# LED_ALERT.net
KiCad netlist of a schematic drawn in Altium Designer
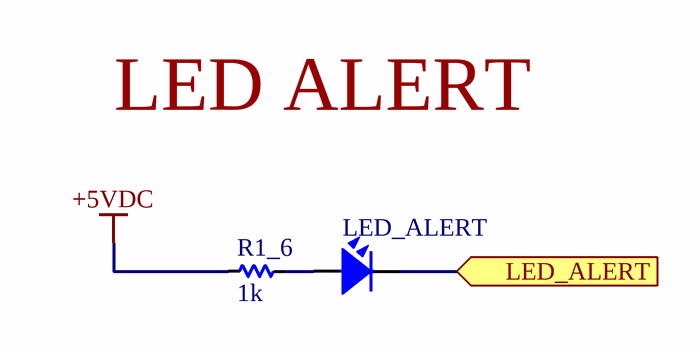
[diagram p0: LED_ALERT.SchDoc]

(export (version "E")
  (design (tool "Eeschema 10.0.6"))
  (components
    (comp (ref "LED_ALERT")
      (value "LED")
      (footprint "LED-3MM-GREEN")
      (description "LED Single colour Green and Red")
      (libsource (lib "Altium Library") (part "LED"))
    )
    (comp (ref "R1_6")
      (value "1k")
      (footprint "RES-SMD-0805")
      (description "Resistor")
      (fields
        (field (name "MANUFACTURER") "Generic Components")
        (field (name "PUBLISHER") "Altium Hobart Technology Centre")
      )
      (libsource (lib "Altium Library") (part "Res-SMD"))
    )
  )
  (nets
    (net (code "1") (name "+5VDC") (class "Default")
      (node (ref "R1_6") (pin "2") (pinfunction "2_2") (pintype "passive"))
    )
    (net (code "2") (name "/LED_ALERT") (class "Default")
      (node (ref "LED_ALERT") (pin "2") (pinfunction "2_2") (pintype "passive"))
    )
    (net (code "3") (name "Net-(LED_ALERT-Pad1)") (class "Default")
      (node (ref "LED_ALERT") (pin "1") (pinfunction "1_1") (pintype "passive"))
      (node (ref "R1_6") (pin "1") (pinfunction "1_1") (pintype "passive"))
    )
  )
)
